# LEDs.net
KiCad netlist of a schematic drawn in Altium Designer
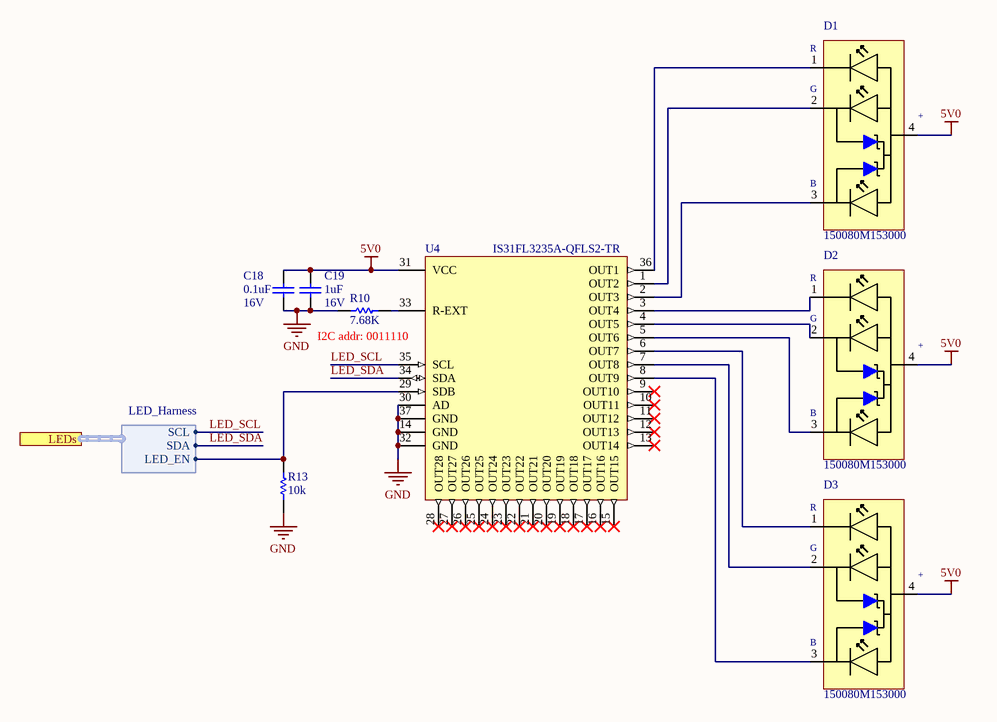
[diagram p0: LEDs.SchDoc]

(export (version "E")
  (design (tool "Eeschema 10.0.6"))
  (components
    (comp (ref "C18")
      (value "0.1uF")
      (footprint "CAPC1005(0402)N")
      (description "CAP CER 0.1UF 16V X5R 0402")
      (fields (field (name "TOLERANCE") "±10%") (field (name "VOLTAGE - RATED") "16V"))
      (libsource (lib "GMLintLib") (part "CAP"))
    )
    (comp (ref "C19")
      (value "1uF")
      (footprint "CAPC1005(0402)N")
      (description "CAP")
      (fields (field (name "TOLERANCE") "±10%") (field (name "VOLTAGE - RATED") "16V"))
      (libsource (lib "GMLintLib") (part "CAP"))
    )
    (comp (ref "D1")
      (value "150080M153000")
      (footprint "*LED_150080M153000")
      (fields (field (name "MF") "Wurth Electronics"))
      (libsource (lib "LegBoard") (part "150080M153000"))
    )
    (comp (ref "D2")
      (value "150080M153000")
      (footprint "*LED_150080M153000")
      (fields (field (name "MF") "Wurth Electronics"))
      (libsource (lib "LegBoard") (part "150080M153000"))
    )
    (comp (ref "D3")
      (value "150080M153000")
      (footprint "*LED_150080M153000")
      (fields (field (name "MF") "Wurth Electronics"))
      (libsource (lib "LegBoard") (part "150080M153000"))
    )
    (comp (ref "R10")
      (value "7.68K")
      (footprint "RESC1005(0402)N")
      (description "Resistor, Chip")
      (libsource (lib "xo-190216") (part "RES"))
    )
    (comp (ref "R13")
      (value "10k")
      (footprint "RESC1005(0402)N")
      (description "Resistor, Chip")
      (libsource (lib "GMLintLib") (part "RES"))
    )
    (comp (ref "U4")
      (value "IS31FL3235A-QFLS2-TR")
      (footprint "QFN40P400X400X80_HS-37N")
      (description "28 channel LED Driver")
      (libsource (lib "billy_misc") (part "IS31FL3235A-QFLS2-TR"))
    )
  )
  (nets
    (net (code "2") (name "/LED_SCL") (class "Default")
      (node (ref "U4") (pin "35") (pinfunction "SCL_35") (pintype "input"))
    )
    (net (code "3") (name "/LED_SDA") (class "Default")
      (node (ref "U4") (pin "34") (pinfunction "SDA_34") (pintype "bidirectional"))
    )
    (net (code "5") (name "5V0") (class "Default")
      (node (ref "C18") (pin "2") (pinfunction "2_2") (pintype "passive"))
      (node (ref "C19") (pin "2") (pinfunction "2_2") (pintype "passive"))
      (node (ref "D1") (pin "4") (pinfunction "A_4") (pintype "passive"))
      (node (ref "D2") (pin "4") (pinfunction "A_4") (pintype "passive"))
      (node (ref "D3") (pin "4") (pinfunction "A_4") (pintype "passive"))
      (node (ref "U4") (pin "31") (pinfunction "VCC_31") (pintype "power_in"))
    )
    (net (code "6") (name "GND") (class "Default")
      (node (ref "C18") (pin "1") (pinfunction "1_1") (pintype "passive"))
      (node (ref "C19") (pin "1") (pinfunction "1_1") (pintype "passive"))
      (node (ref "R10") (pin "1") (pinfunction "1_1") (pintype "passive"))
      (node (ref "R13") (pin "1") (pinfunction "1_1") (pintype "passive"))
      (node (ref "U4") (pin "14") (pinfunction "GND_14") (pintype "power_in"))
      (node (ref "U4") (pin "30") (pinfunction "AD_30") (pintype "passive"))
      (node (ref "U4") (pin "32") (pinfunction "GND_32") (pintype "power_in"))
      (node (ref "U4") (pin "37") (pinfunction "GND_37") (pintype "passive"))
    )
    (net (code "7") (name "Net-(D1-B)") (class "Default")
      (node (ref "D1") (pin "3") (pinfunction "B_3") (pintype "passive"))
      (node (ref "U4") (pin "2") (pinfunction "OUT3_2") (pintype "output"))
    )
    (net (code "8") (name "Net-(D1-G)") (class "Default")
      (node (ref "D1") (pin "2") (pinfunction "G_2") (pintype "passive"))
      (node (ref "U4") (pin "1") (pinfunction "OUT2_1") (pintype "output"))
    )
    (net (code "9") (name "Net-(D1-R)") (class "Default")
      (node (ref "D1") (pin "1") (pinfunction "R_1") (pintype "passive"))
      (node (ref "U4") (pin "36") (pinfunction "OUT1_36") (pintype "output"))
    )
    (net (code "10") (name "Net-(D2-B)") (class "Default")
      (node (ref "D2") (pin "3") (pinfunction "B_3") (pintype "passive"))
      (node (ref "U4") (pin "5") (pinfunction "OUT6_5") (pintype "output"))
    )
    (net (code "11") (name "Net-(D2-G)") (class "Default")
      (node (ref "D2") (pin "2") (pinfunction "G_2") (pintype "passive"))
      (node (ref "U4") (pin "4") (pinfunction "OUT5_4") (pintype "output"))
    )
    (net (code "12") (name "Net-(D2-R)") (class "Default")
      (node (ref "D2") (pin "1") (pinfunction "R_1") (pintype "passive"))
      (node (ref "U4") (pin "3") (pinfunction "OUT4_3") (pintype "output"))
    )
    (net (code "13") (name "Net-(D3-B)") (class "Default")
      (node (ref "D3") (pin "3") (pinfunction "B_3") (pintype "passive"))
      (node (ref "U4") (pin "8") (pinfunction "OUT9_8") (pintype "output"))
    )
    (net (code "14") (name "Net-(D3-G)") (class "Default")
      (node (ref "D3") (pin "2") (pinfunction "G_2") (pintype "passive"))
      (node (ref "U4") (pin "7") (pinfunction "OUT8_7") (pintype "output"))
    )
    (net (code "15") (name "Net-(D3-R)") (class "Default")
      (node (ref "D3") (pin "1") (pinfunction "R_1") (pintype "passive"))
      (node (ref "U4") (pin "6") (pinfunction "OUT7_6") (pintype "output"))
    )
    (net (code "16") (name "Net-(U4-R-EXT)") (class "Default")
      (node (ref "R10") (pin "2") (pinfunction "2_2") (pintype "passive"))
      (node (ref "U4") (pin "33") (pinfunction "R-EXT_33") (pintype "passive"))
    )
    (net (code "17") (name "Net-(U4-SDB)") (class "Default")
      (node (ref "R13") (pin "2") (pinfunction "2_2") (pintype "passive"))
      (node (ref "U4") (pin "29") (pinfunction "SDB_29") (pintype "input"))
    )
    (net (code "18") (name "unconnected-(U4-OUT10-Pad9)") (class "Default")
      (node (ref "U4") (pin "9") (pinfunction "OUT10_9") (pintype "output+no_connect"))
    )
    (net (code "19") (name "unconnected-(U4-OUT11-Pad10)") (class "Default")
      (node (ref "U4") (pin "10") (pinfunction "OUT11_10") (pintype "output+no_connect"))
    )
    (net (code "20") (name "unconnected-(U4-OUT12-Pad11)") (class "Default")
      (node (ref "U4") (pin "11") (pinfunction "OUT12_11") (pintype "output+no_connect"))
    )
    (net (code "21") (name "unconnected-(U4-OUT13-Pad12)") (class "Default")
      (node (ref "U4") (pin "12") (pinfunction "OUT13_12") (pintype "output+no_connect"))
    )
    (net (code "22") (name "unconnected-(U4-OUT14-Pad13)") (class "Default")
      (node (ref "U4") (pin "13") (pinfunction "OUT14_13") (pintype "output+no_connect"))
    )
    (net (code "23") (name "unconnected-(U4-OUT15-Pad15)") (class "Default")
      (node (ref "U4") (pin "15") (pinfunction "OUT15_15") (pintype "output+no_connect"))
    )
    (net (code "24") (name "unconnected-(U4-OUT16-Pad16)") (class "Default")
      (node (ref "U4") (pin "16") (pinfunction "OUT16_16") (pintype "output+no_connect"))
    )
    (net (code "25") (name "unconnected-(U4-OUT17-Pad17)") (class "Default")
      (node (ref "U4") (pin "17") (pinfunction "OUT17_17") (pintype "output+no_connect"))
    )
    (net (code "26") (name "unconnected-(U4-OUT18-Pad18)") (class "Default")
      (node (ref "U4") (pin "18") (pinfunction "OUT18_18") (pintype "output+no_connect"))
    )
    (net (code "27") (name "unconnected-(U4-OUT19-Pad19)") (class "Default")
      (node (ref "U4") (pin "19") (pinfunction "OUT19_19") (pintype "output+no_connect"))
    )
    (net (code "28") (name "unconnected-(U4-OUT20-Pad20)") (class "Default")
      (node (ref "U4") (pin "20") (pinfunction "OUT20_20") (pintype "output+no_connect"))
    )
    (net (code "29") (name "unconnected-(U4-OUT21-Pad21)") (class "Default")
      (node (ref "U4") (pin "21") (pinfunction "OUT21_21") (pintype "output+no_connect"))
    )
    (net (code "30") (name "unconnected-(U4-OUT22-Pad22)") (class "Default")
      (node (ref "U4") (pin "22") (pinfunction "OUT22_22") (pintype "output+no_connect"))
    )
    (net (code "31") (name "unconnected-(U4-OUT23-Pad23)") (class "Default")
      (node (ref "U4") (pin "23") (pinfunction "OUT23_23") (pintype "output+no_connect"))
    )
    (net (code "32") (name "unconnected-(U4-OUT24-Pad24)") (class "Default")
      (node (ref "U4") (pin "24") (pinfunction "OUT24_24") (pintype "output+no_connect"))
    )
    (net (code "33") (name "unconnected-(U4-OUT25-Pad25)") (class "Default")
      (node (ref "U4") (pin "25") (pinfunction "OUT25_25") (pintype "output+no_connect"))
    )
    (net (code "34") (name "unconnected-(U4-OUT26-Pad26)") (class "Default")
      (node (ref "U4") (pin "26") (pinfunction "OUT26_26") (pintype "output+no_connect"))
    )
    (net (code "35") (name "unconnected-(U4-OUT27-Pad27)") (class "Default")
      (node (ref "U4") (pin "27") (pinfunction "OUT27_27") (pintype "output+no_connect"))
    )
    (net (code "36") (name "unconnected-(U4-OUT28-Pad28)") (class "Default")
      (node (ref "U4") (pin "28") (pinfunction "OUT28_28") (pintype "output+no_connect"))
    )
  )
)
